# muxes.net
KiCad netlist of a schematic drawn in Altium Designer
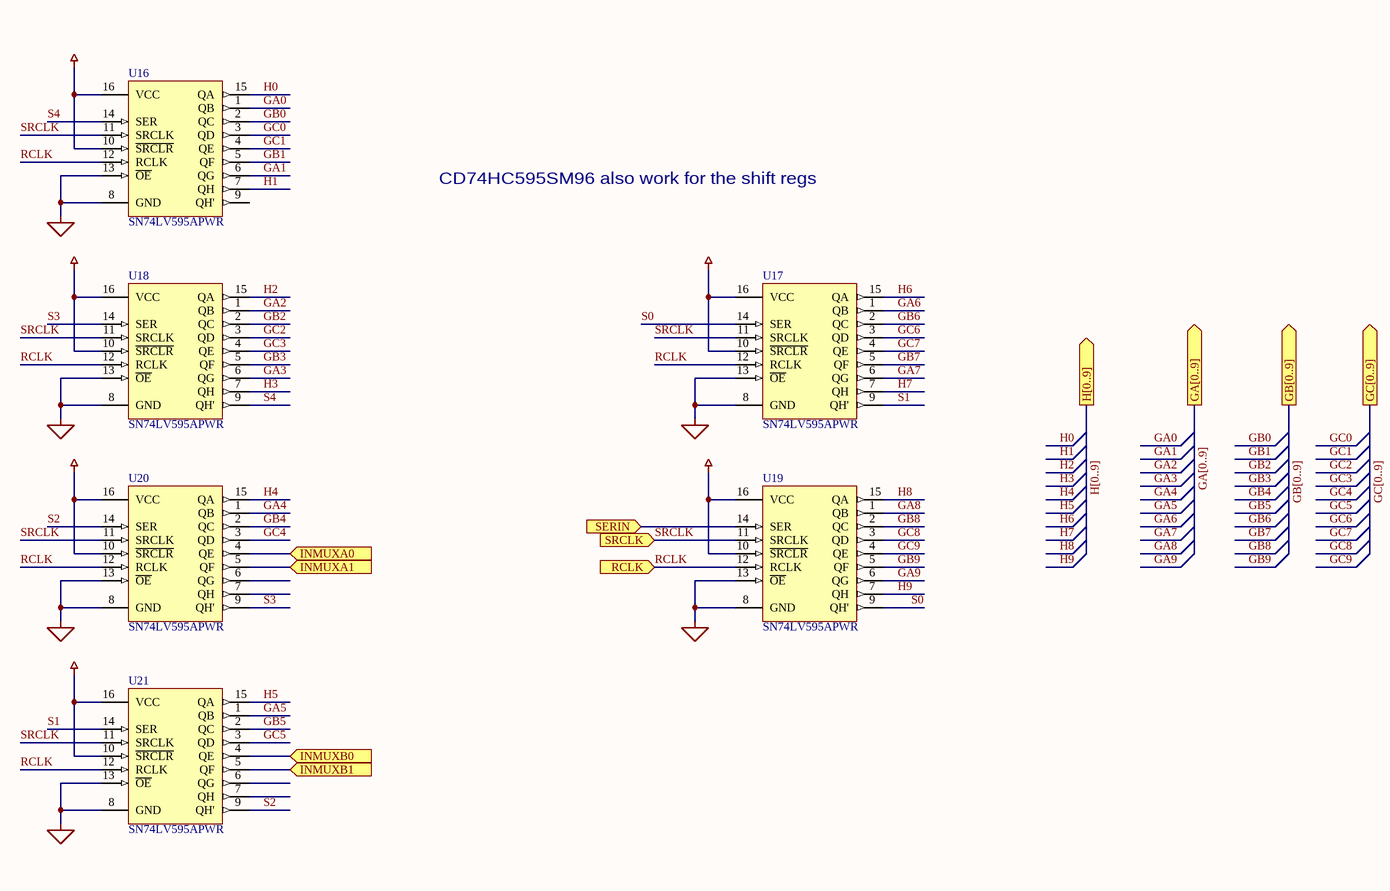
[diagram p0: muxes.SCHDOC]

(export (version "E")
  (design (tool "Eeschema 10.0.6"))
  (components
    (comp (ref "U16")
      (value "SN74LV595APWR")
      (footprint "SSO-G16/X.4")
      (description "8-bit shift register with 3-state output")
      (libsource (lib "parts") (part "SN74LV595APWR"))
    )
    (comp (ref "U17")
      (value "SN74LV595APWR")
      (footprint "SSO-G16/X.4")
      (description "8-bit shift register with 3-state output")
      (libsource (lib "parts") (part "SN74LV595APWR"))
    )
    (comp (ref "U18")
      (value "SN74LV595APWR")
      (footprint "SSO-G16/X.4")
      (description "8-bit shift register with 3-state output")
      (libsource (lib "parts") (part "SN74LV595APWR"))
    )
    (comp (ref "U19")
      (value "SN74LV595APWR")
      (footprint "SSO-G16/X.4")
      (description "8-bit shift register with 3-state output")
      (libsource (lib "parts") (part "SN74LV595APWR"))
    )
    (comp (ref "U20")
      (value "SN74LV595APWR")
      (footprint "SSO-G16/X.4")
      (description "8-bit shift register with 3-state output")
      (libsource (lib "parts") (part "SN74LV595APWR"))
    )
    (comp (ref "U21")
      (value "SN74LV595APWR")
      (footprint "SSO-G16/X.4")
      (description "8-bit shift register with 3-state output")
      (libsource (lib "parts") (part "SN74LV595APWR"))
    )
  )
  (nets
    (net (code "1") (name "/GA0") (class "Default")
      (node (ref "U16") (pin "1") (pinfunction "QB_1") (pintype "output"))
    )
    (net (code "2") (name "/GA1") (class "Default")
      (node (ref "U16") (pin "6") (pinfunction "QG_6") (pintype "output"))
    )
    (net (code "3") (name "/GA2") (class "Default")
      (node (ref "U18") (pin "1") (pinfunction "QB_1") (pintype "output"))
    )
    (net (code "4") (name "/GA3") (class "Default")
      (node (ref "U18") (pin "6") (pinfunction "QG_6") (pintype "output"))
    )
    (net (code "5") (name "/GA4") (class "Default")
      (node (ref "U20") (pin "1") (pinfunction "QB_1") (pintype "output"))
    )
    (net (code "6") (name "/GA5") (class "Default")
      (node (ref "U21") (pin "1") (pinfunction "QB_1") (pintype "output"))
    )
    (net (code "7") (name "/GA6") (class "Default")
      (node (ref "U17") (pin "1") (pinfunction "QB_1") (pintype "output"))
    )
    (net (code "8") (name "/GA7") (class "Default")
      (node (ref "U17") (pin "6") (pinfunction "QG_6") (pintype "output"))
    )
    (net (code "9") (name "/GA8") (class "Default")
      (node (ref "U19") (pin "1") (pinfunction "QB_1") (pintype "output"))
    )
    (net (code "10") (name "/GA9") (class "Default")
      (node (ref "U19") (pin "6") (pinfunction "QG_6") (pintype "output"))
    )
    (net (code "12") (name "/GB0") (class "Default")
      (node (ref "U16") (pin "2") (pinfunction "QC_2") (pintype "output"))
    )
    (net (code "13") (name "/GB1") (class "Default")
      (node (ref "U16") (pin "5") (pinfunction "QF_5") (pintype "output"))
    )
    (net (code "14") (name "/GB2") (class "Default")
      (node (ref "U18") (pin "2") (pinfunction "QC_2") (pintype "output"))
    )
    (net (code "15") (name "/GB3") (class "Default")
      (node (ref "U18") (pin "5") (pinfunction "QF_5") (pintype "output"))
    )
    (net (code "16") (name "/GB4") (class "Default")
      (node (ref "U20") (pin "2") (pinfunction "QC_2") (pintype "output"))
    )
    (net (code "17") (name "/GB5") (class "Default")
      (node (ref "U21") (pin "2") (pinfunction "QC_2") (pintype "output"))
    )
    (net (code "18") (name "/GB6") (class "Default")
      (node (ref "U17") (pin "2") (pinfunction "QC_2") (pintype "output"))
    )
    (net (code "19") (name "/GB7") (class "Default")
      (node (ref "U17") (pin "5") (pinfunction "QF_5") (pintype "output"))
    )
    (net (code "20") (name "/GB8") (class "Default")
      (node (ref "U19") (pin "2") (pinfunction "QC_2") (pintype "output"))
    )
    (net (code "21") (name "/GB9") (class "Default")
      (node (ref "U19") (pin "5") (pinfunction "QF_5") (pintype "output"))
    )
    (net (code "23") (name "/GC0") (class "Default")
      (node (ref "U16") (pin "3") (pinfunction "QD_3") (pintype "output"))
    )
    (net (code "24") (name "/GC1") (class "Default")
      (node (ref "U16") (pin "4") (pinfunction "QE_4") (pintype "output"))
    )
    (net (code "25") (name "/GC2") (class "Default")
      (node (ref "U18") (pin "3") (pinfunction "QD_3") (pintype "output"))
    )
    (net (code "26") (name "/GC3") (class "Default")
      (node (ref "U18") (pin "4") (pinfunction "QE_4") (pintype "output"))
    )
    (net (code "27") (name "/GC4") (class "Default")
      (node (ref "U20") (pin "3") (pinfunction "QD_3") (pintype "output"))
    )
    (net (code "28") (name "/GC5") (class "Default")
      (node (ref "U21") (pin "3") (pinfunction "QD_3") (pintype "output"))
    )
    (net (code "29") (name "/GC6") (class "Default")
      (node (ref "U17") (pin "3") (pinfunction "QD_3") (pintype "output"))
    )
    (net (code "30") (name "/GC7") (class "Default")
      (node (ref "U17") (pin "4") (pinfunction "QE_4") (pintype "output"))
    )
    (net (code "31") (name "/GC8") (class "Default")
      (node (ref "U19") (pin "3") (pinfunction "QD_3") (pintype "output"))
    )
    (net (code "32") (name "/GC9") (class "Default")
      (node (ref "U19") (pin "4") (pinfunction "QE_4") (pintype "output"))
    )
    (net (code "34") (name "/H0") (class "Default")
      (node (ref "U16") (pin "15") (pinfunction "QA_15") (pintype "output"))
    )
    (net (code "35") (name "/H1") (class "Default")
      (node (ref "U16") (pin "7") (pinfunction "QH_7") (pintype "output"))
    )
    (net (code "36") (name "/H2") (class "Default")
      (node (ref "U18") (pin "15") (pinfunction "QA_15") (pintype "output"))
    )
    (net (code "37") (name "/H3") (class "Default")
      (node (ref "U18") (pin "7") (pinfunction "QH_7") (pintype "output"))
    )
    (net (code "38") (name "/H4") (class "Default")
      (node (ref "U20") (pin "15") (pinfunction "QA_15") (pintype "output"))
    )
    (net (code "39") (name "/H5") (class "Default")
      (node (ref "U21") (pin "15") (pinfunction "QA_15") (pintype "output"))
    )
    (net (code "40") (name "/H6") (class "Default")
      (node (ref "U17") (pin "15") (pinfunction "QA_15") (pintype "output"))
    )
    (net (code "41") (name "/H7") (class "Default")
      (node (ref "U17") (pin "7") (pinfunction "QH_7") (pintype "output"))
    )
    (net (code "42") (name "/H8") (class "Default")
      (node (ref "U19") (pin "15") (pinfunction "QA_15") (pintype "output"))
    )
    (net (code "43") (name "/H9") (class "Default")
      (node (ref "U19") (pin "7") (pinfunction "QH_7") (pintype "output"))
    )
    (net (code "45") (name "/INMUXA0") (class "Default")
      (node (ref "U20") (pin "4") (pinfunction "QE_4") (pintype "output"))
    )
    (net (code "46") (name "/INMUXA1") (class "Default")
      (node (ref "U20") (pin "5") (pinfunction "QF_5") (pintype "output"))
    )
    (net (code "47") (name "/INMUXB0") (class "Default")
      (node (ref "U21") (pin "4") (pinfunction "QE_4") (pintype "output"))
    )
    (net (code "48") (name "/INMUXB1") (class "Default")
      (node (ref "U21") (pin "5") (pinfunction "QF_5") (pintype "output"))
    )
    (net (code "49") (name "/RCLK") (class "Default")
      (node (ref "U16") (pin "12") (pinfunction "RCLK_12") (pintype "input"))
      (node (ref "U17") (pin "12") (pinfunction "RCLK_12") (pintype "input"))
      (node (ref "U18") (pin "12") (pinfunction "RCLK_12") (pintype "input"))
      (node (ref "U19") (pin "12") (pinfunction "RCLK_12") (pintype "input"))
      (node (ref "U20") (pin "12") (pinfunction "RCLK_12") (pintype "input"))
      (node (ref "U21") (pin "12") (pinfunction "RCLK_12") (pintype "input"))
    )
    (net (code "50") (name "/S0") (class "Default")
      (node (ref "U17") (pin "14") (pinfunction "SER_14") (pintype "input"))
      (node (ref "U19") (pin "9") (pinfunction "QH'_9") (pintype "output"))
    )
    (net (code "51") (name "/S1") (class "Default")
      (node (ref "U17") (pin "9") (pinfunction "QH'_9") (pintype "output"))
      (node (ref "U21") (pin "14") (pinfunction "SER_14") (pintype "input"))
    )
    (net (code "52") (name "/S2") (class "Default")
      (node (ref "U20") (pin "14") (pinfunction "SER_14") (pintype "input"))
      (node (ref "U21") (pin "9") (pinfunction "QH'_9") (pintype "output"))
    )
    (net (code "53") (name "/S3") (class "Default")
      (node (ref "U18") (pin "14") (pinfunction "SER_14") (pintype "input"))
      (node (ref "U20") (pin "9") (pinfunction "QH'_9") (pintype "output"))
    )
    (net (code "54") (name "/S4") (class "Default")
      (node (ref "U16") (pin "14") (pinfunction "SER_14") (pintype "input"))
      (node (ref "U18") (pin "9") (pinfunction "QH'_9") (pintype "output"))
    )
    (net (code "55") (name "/SERIN") (class "Default")
      (node (ref "U19") (pin "14") (pinfunction "SER_14") (pintype "input"))
    )
    (net (code "56") (name "/SRCLK") (class "Default")
      (node (ref "U16") (pin "11") (pinfunction "SRCLK_11") (pintype "input"))
      (node (ref "U17") (pin "11") (pinfunction "SRCLK_11") (pintype "input"))
      (node (ref "U18") (pin "11") (pinfunction "SRCLK_11") (pintype "input"))
      (node (ref "U19") (pin "11") (pinfunction "SRCLK_11") (pintype "input"))
      (node (ref "U20") (pin "11") (pinfunction "SRCLK_11") (pintype "input"))
      (node (ref "U21") (pin "11") (pinfunction "SRCLK_11") (pintype "input"))
    )
    (net (code "57") (name "AGND") (class "Default")
      (node (ref "U16") (pin "13") (pinfunction "~{OE}_13") (pintype "input"))
      (node (ref "U16") (pin "8") (pinfunction "GND_8") (pintype "power_in"))
      (node (ref "U17") (pin "13") (pinfunction "~{OE}_13") (pintype "input"))
      (node (ref "U17") (pin "8") (pinfunction "GND_8") (pintype "power_in"))
      (node (ref "U18") (pin "13") (pinfunction "~{OE}_13") (pintype "input"))
      (node (ref "U18") (pin "8") (pinfunction "GND_8") (pintype "power_in"))
      (node (ref "U19") (pin "13") (pinfunction "~{OE}_13") (pintype "input"))
      (node (ref "U19") (pin "8") (pinfunction "GND_8") (pintype "power_in"))
      (node (ref "U20") (pin "13") (pinfunction "~{OE}_13") (pintype "input"))
      (node (ref "U20") (pin "8") (pinfunction "GND_8") (pintype "power_in"))
      (node (ref "U21") (pin "13") (pinfunction "~{OE}_13") (pintype "input"))
      (node (ref "U21") (pin "8") (pinfunction "GND_8") (pintype "power_in"))
    )
    (net (code "58") (name "AVDD") (class "Default")
      (node (ref "U16") (pin "10") (pinfunction "~{SRCLR}_10") (pintype "input"))
      (node (ref "U16") (pin "16") (pinfunction "VCC_16") (pintype "power_in"))
      (node (ref "U17") (pin "10") (pinfunction "~{SRCLR}_10") (pintype "input"))
      (node (ref "U17") (pin "16") (pinfunction "VCC_16") (pintype "power_in"))
      (node (ref "U18") (pin "10") (pinfunction "~{SRCLR}_10") (pintype "input"))
      (node (ref "U18") (pin "16") (pinfunction "VCC_16") (pintype "power_in"))
      (node (ref "U19") (pin "10") (pinfunction "~{SRCLR}_10") (pintype "input"))
      (node (ref "U19") (pin "16") (pinfunction "VCC_16") (pintype "power_in"))
      (node (ref "U20") (pin "10") (pinfunction "~{SRCLR}_10") (pintype "input"))
      (node (ref "U20") (pin "16") (pinfunction "VCC_16") (pintype "power_in"))
      (node (ref "U21") (pin "10") (pinfunction "~{SRCLR}_10") (pintype "input"))
      (node (ref "U21") (pin "16") (pinfunction "VCC_16") (pintype "power_in"))
    )
    (net (code "59") (name "unconnected-(U16-QH'-Pad9)") (class "Default")
      (node (ref "U16") (pin "9") (pinfunction "QH'_9") (pintype "output"))
    )
    (net (code "60") (name "unconnected-(U20-QG-Pad6)") (class "Default")
      (node (ref "U20") (pin "6") (pinfunction "QG_6") (pintype "output"))
    )
    (net (code "61") (name "unconnected-(U20-QH-Pad7)") (class "Default")
      (node (ref "U20") (pin "7") (pinfunction "QH_7") (pintype "output"))
    )
    (net (code "62") (name "unconnected-(U21-QG-Pad6)") (class "Default")
      (node (ref "U21") (pin "6") (pinfunction "QG_6") (pintype "output"))
    )
    (net (code "63") (name "unconnected-(U21-QH-Pad7)") (class "Default")
      (node (ref "U21") (pin "7") (pinfunction "QH_7") (pintype "output"))
    )
  )
)
